# AutoTimer_List1.net
KiCad netlist of a schematic drawn in Altium Designer
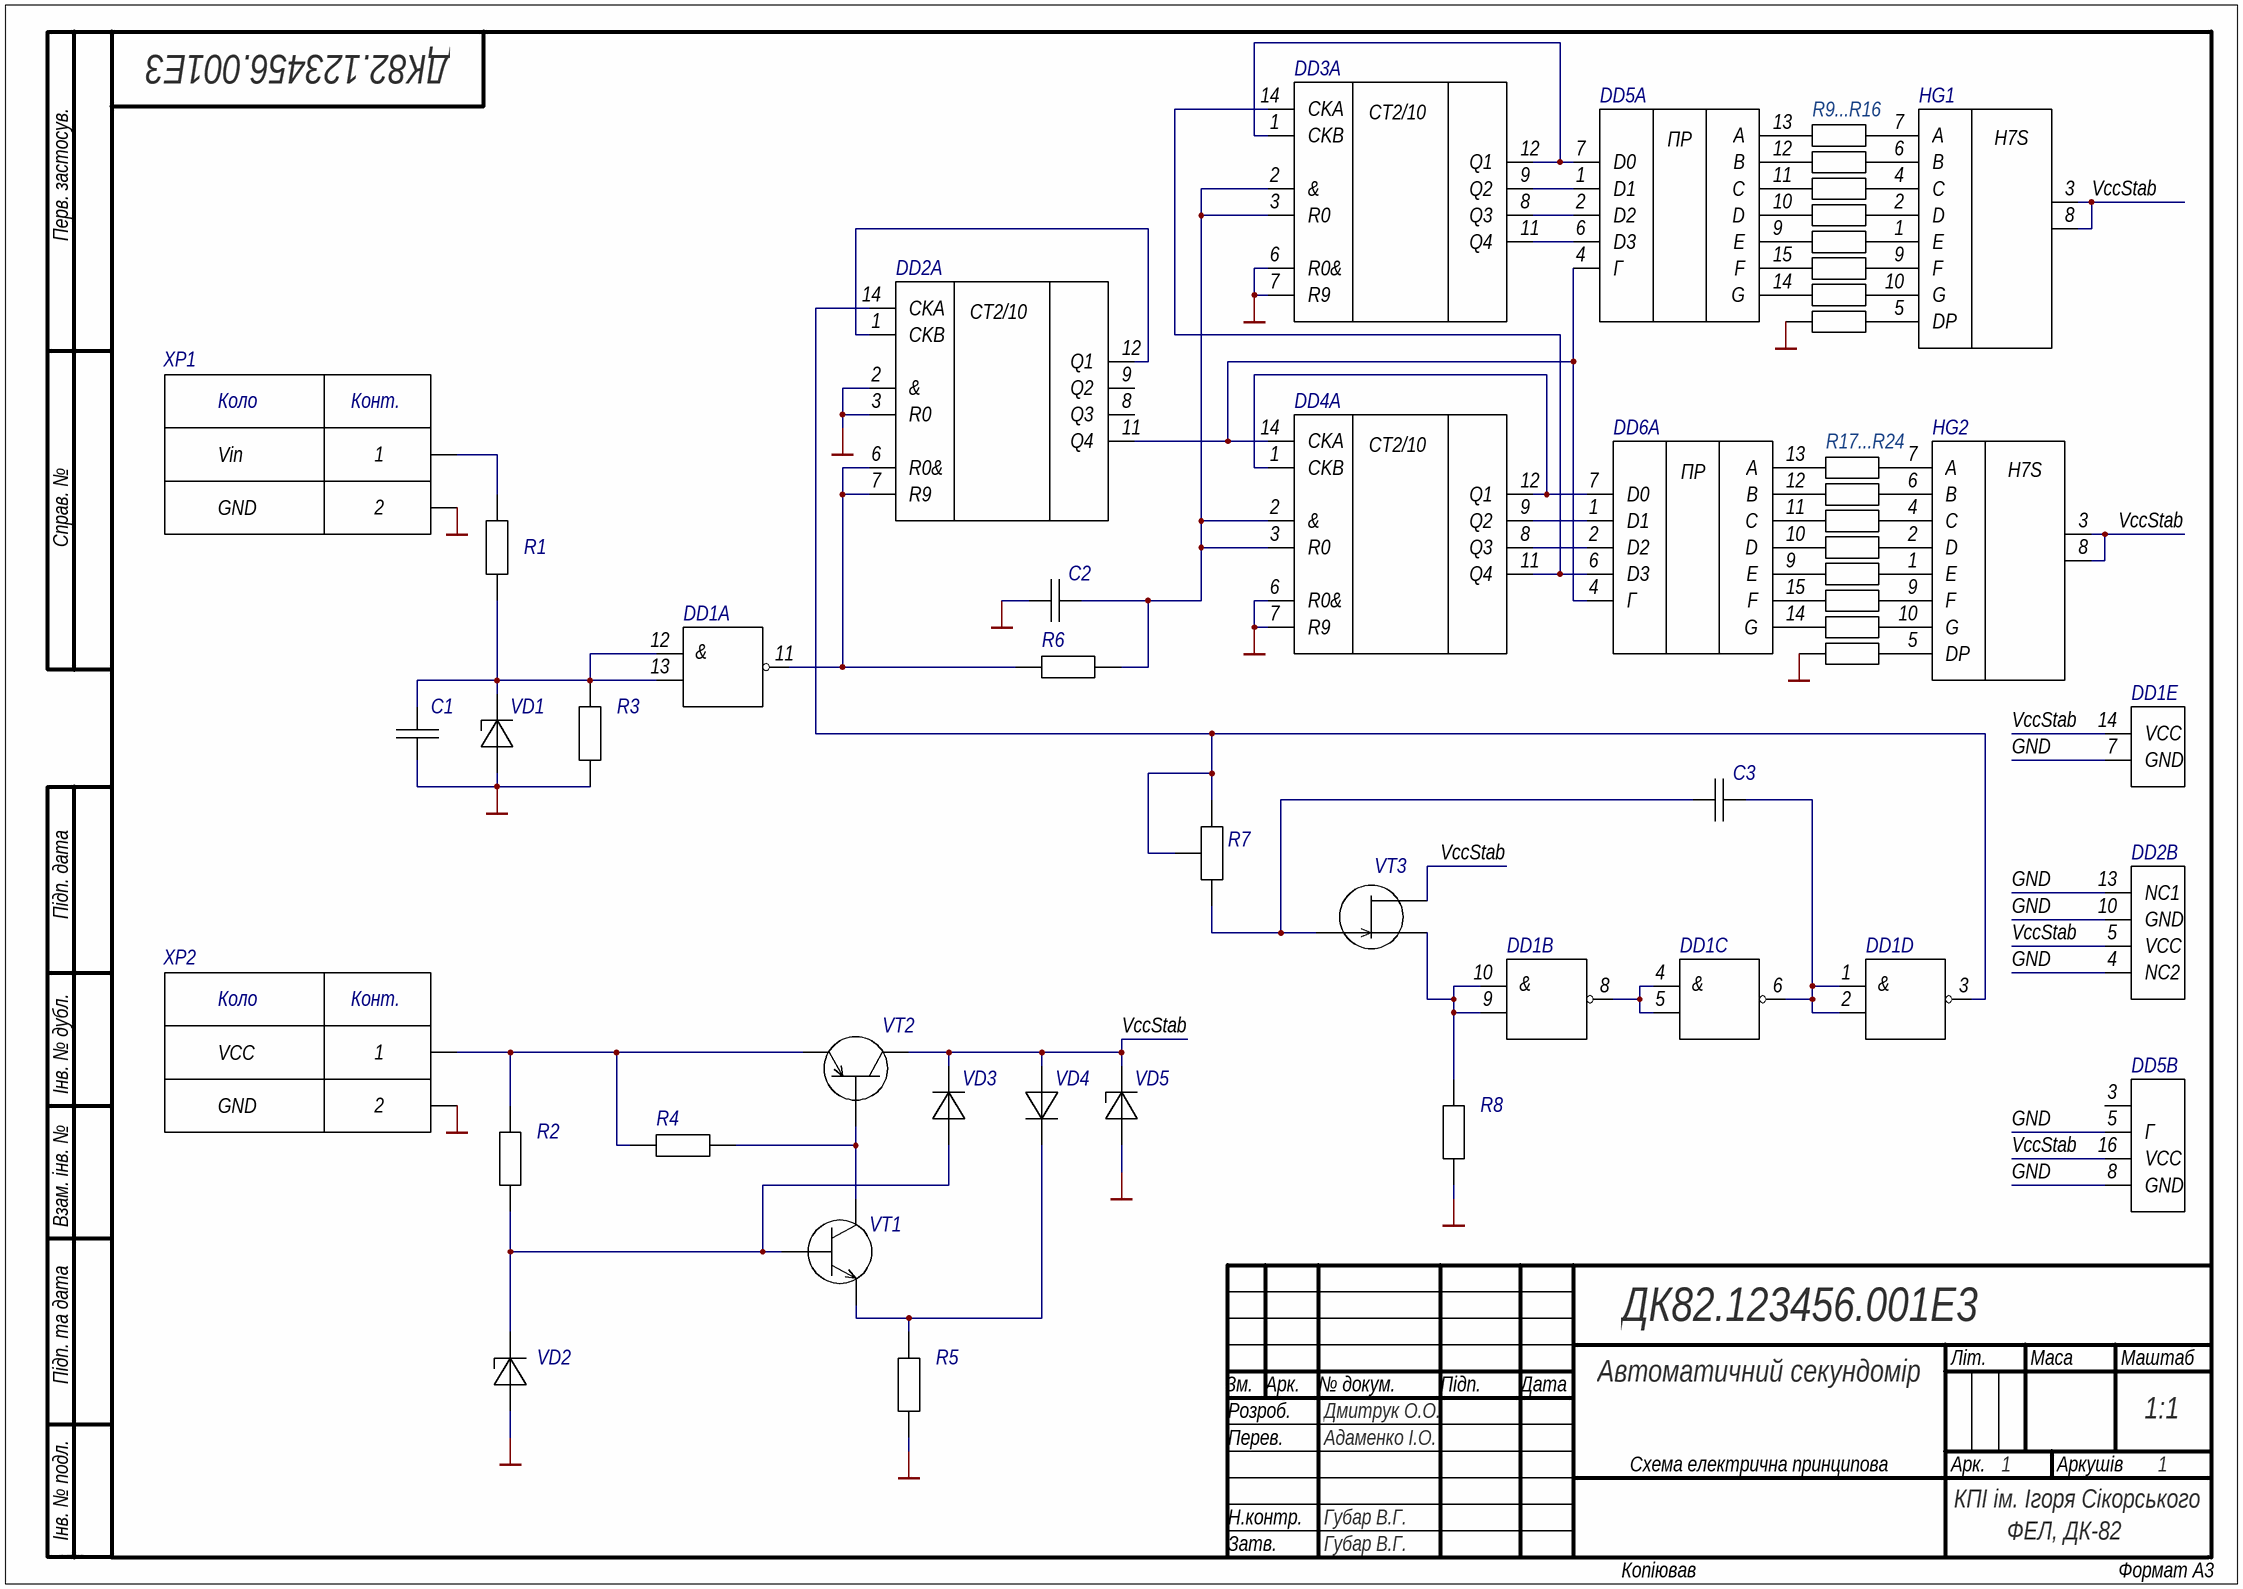
[diagram p0: AutoTimer_List1.SchDoc]

(export (version "E")
  (design (tool "Eeschema 10.0.6"))
  (components
    (comp (ref "C1")
      (value "С-0805 50 В 4,7 мкФ 10% X7R KEMET")
      (footprint "0805")
      (description "0805")
      (fields (field (name "VOLTAGE") "50 В") (field (name "TOLERANCE") "10%"))
      (libsource (lib "AutoTimer") (part "C-0805 4,7мкФ"))
    )
    (comp (ref "C2")
      (value "С-0805 50 В 1 мкФ 10% X7R KEMET")
      (footprint "0805")
      (description "0805")
      (fields (field (name "VOLTAGE") "50 В") (field (name "TOLERANCE") "10%"))
      (libsource (lib "AutoTimer") (part "C-0805 1мкФ"))
    )
    (comp (ref "C3")
      (value "С-0805 50 В 1 мкФ 10% X7R KEMET")
      (footprint "0805")
      (description "0805")
      (fields (field (name "VOLTAGE") "50 В") (field (name "TOLERANCE") "10%"))
      (libsource (lib "AutoTimer") (part "C-0805 1мкФ"))
    )
    (comp (ref "DD1")
      (value "SN74LS00 Texas Insturments")
      (footprint "SN74LS00 SN74LS90 FOOTPRINT")
      (fields
        (field (name "MANUFACTURER") "Texas Insturments")
        (field (name "COMPONENTLINK1URL") "file:///C:/Users/aleks/Downloads/Telegram%20Desktop/sn7400-sp.pdf")
      )
      (libsource (lib "AutoTimer") (part "SN74LS00"))
    )
    (comp (ref "DD2")
      (value "SN74LS90 Texas Insturments")
      (footprint "SN74LS00 SN74LS90 FOOTPRINT")
      (fields
        (field (name "MANUFACTURER") "Texas Insturments")
        (field (name "COMPONENTLINK1URL") "file:///C:/Users/aleks/Downloads/Telegram%20Desktop/SN7490AN.pdf")
      )
      (libsource (lib "AutoTimer") (part "SN74LS90"))
    )
    (comp (ref "DD3")
      (value "SN74LS90 Texas Insturments")
      (footprint "SN74LS00 SN74LS90 FOOTPRINT")
      (fields
        (field (name "MANUFACTURER") "Texas Insturments")
        (field (name "COMPONENTLINK1URL") "file:///C:/Users/aleks/Downloads/Telegram%20Desktop/SN7490AN.pdf")
      )
      (libsource (lib "AutoTimer") (part "SN74LS90"))
    )
    (comp (ref "DD4")
      (value "SN74LS90 Texas Insturments")
      (footprint "SN74LS00 SN74LS90 FOOTPRINT")
      (fields
        (field (name "MANUFACTURER") "Texas Insturments")
        (field (name "COMPONENTLINK1URL") "file:///C:/Users/aleks/Downloads/Telegram%20Desktop/SN7490AN.pdf")
      )
      (libsource (lib "AutoTimer") (part "SN74LS90"))
    )
    (comp (ref "DD5")
      (value "К514ПР1 *")
      (footprint "К514ПР1 FOOTPRINT")
      (libsource (lib "AutoTimer") (part "К514ПР1"))
    )
    (comp (ref "DD6")
      (value "К514ПР1 *")
      (footprint "К514ПР1 FOOTPRINT")
      (libsource (lib "AutoTimer") (part "К514ПР1"))
    )
    (comp (ref "HG1")
      (value "KCSA56-105 Kingbright")
      (footprint "KCSA56-105_FOOTPRINT")
      (fields (field (name "MANUFACTURER") "Kingbright"))
      (libsource (lib "AutoTimer") (part "KCSA56-105"))
    )
    (comp (ref "HG2")
      (value "KCSA56-105 Kingbright")
      (footprint "KCSA56-105_FOOTPRINT")
      (fields (field (name "MANUFACTURER") "Kingbright"))
      (libsource (lib "AutoTimer") (part "KCSA56-105"))
    )
    (comp (ref "R1")
      (value "R-0805 0,125 Вт 6,2 кОм 5% Yageo")
      (footprint "0805")
      (fields
        (field (name "POWER") "0,125 Вт")
        (field (name "TOLERANCE") "5%")
        (field (name "MANUFACTURER") "Yageo")
      )
      (libsource (lib "AutoTimer") (part "R-0805 6,2кОм"))
    )
    (comp (ref "R2")
      (value "R-0805 0,125 Вт 3 кОм 5% Yageo")
      (footprint "0805")
      (fields
        (field (name "POWER") "0,125 Вт")
        (field (name "TOLERANCE") "5%")
        (field (name "MANUFACTURER") "Yageo")
      )
      (libsource (lib "AutoTimer") (part "R-0805 3кОм"))
    )
    (comp (ref "R3")
      (value "R-0805 0,125 Вт 2 кОм 5% Yageo")
      (footprint "0805")
      (fields
        (field (name "POWER") "0,125 Вт")
        (field (name "TOLERANCE") "5%")
        (field (name "MANUFACTURER") "Yageo")
      )
      (libsource (lib "AutoTimer") (part "R-0805 2кОм"))
    )
    (comp (ref "R4")
      (value "R-0805 0,125 Вт 510 Ом 5% Yageo")
      (footprint "0805")
      (fields
        (field (name "POWER") "0,125 Вт")
        (field (name "TOLERANCE") "5%")
        (field (name "MANUFACTURER") "Yageo")
      )
      (libsource (lib "AutoTimer") (part "R-0805 510Ом"))
    )
    (comp (ref "R5")
      (value "R-0805 0,125 Вт 390 Ом 5% Yageo")
      (footprint "0805")
      (fields
        (field (name "POWER") "0,125 Вт")
        (field (name "TOLERANCE") "5%")
        (field (name "MANUFACTURER") "Yageo")
      )
      (libsource (lib "AutoTimer") (part "R-0805 390Ом"))
    )
    (comp (ref "R6")
      (value "R-0805 0,125 Вт 1,2 кОм 5% Yageo")
      (footprint "0805")
      (fields
        (field (name "POWER") "0,125 Вт")
        (field (name "TOLERANCE") "5%")
        (field (name "MANUFACTURER") "Yageo")
      )
      (libsource (lib "AutoTimer") (part "R-0805 1,2кОм"))
    )
    (comp (ref "R7")
      (value "3313J-1 0,125 Вт 10 кОм 20% Mouzer")
      (footprint "R-3313J-1 FOOTPRINT")
      (fields
        (field (name "POWER") "0,125 Вт")
        (field (name "TOLERANCE") "20%")
        (field (name "MANUFACTURER") "Mouzer")
      )
      (libsource (lib "AutoTimer") (part "R-3313J-1 10кОм"))
    )
    (comp (ref "R8")
      (value "R-0805 0,125 Вт 300 Ом 5% Yageo")
      (footprint "0805")
      (fields
        (field (name "POWER") "0,125 Вт")
        (field (name "TOLERANCE") "5%")
        (field (name "MANUFACTURER") "Yageo")
      )
      (libsource (lib "AutoTimer") (part "R-0805 300Ом"))
    )
    (comp (ref "R9")
      (value "R-0805 0,125 Вт 240 Ом 5% Yageo")
      (footprint "0805")
      (fields
        (field (name "POWER") "0,125 Вт")
        (field (name "TOLERANCE") "5%")
        (field (name "MANUFACTURER") "Yageo")
      )
      (libsource (lib "AutoTimer") (part "R-0805 240Ом"))
    )
    (comp (ref "R10")
      (value "R-0805 0,125 Вт 240 Ом 5% Yageo")
      (footprint "0805")
      (fields
        (field (name "POWER") "0,125 Вт")
        (field (name "TOLERANCE") "5%")
        (field (name "MANUFACTURER") "Yageo")
      )
      (libsource (lib "AutoTimer") (part "R-0805 240Ом"))
    )
    (comp (ref "R11")
      (value "R-0805 0,125 Вт 240 Ом 5% Yageo")
      (footprint "0805")
      (fields
        (field (name "POWER") "0,125 Вт")
        (field (name "TOLERANCE") "5%")
        (field (name "MANUFACTURER") "Yageo")
      )
      (libsource (lib "AutoTimer") (part "R-0805 240Ом"))
    )
    (comp (ref "R12")
      (value "R-0805 0,125 Вт 240 Ом 5% Yageo")
      (footprint "0805")
      (fields
        (field (name "POWER") "0,125 Вт")
        (field (name "TOLERANCE") "5%")
        (field (name "MANUFACTURER") "Yageo")
      )
      (libsource (lib "AutoTimer") (part "R-0805 240Ом"))
    )
    (comp (ref "R13")
      (value "R-0805 0,125 Вт 240 Ом 5% Yageo")
      (footprint "0805")
      (fields
        (field (name "POWER") "0,125 Вт")
        (field (name "TOLERANCE") "5%")
        (field (name "MANUFACTURER") "Yageo")
      )
      (libsource (lib "AutoTimer") (part "R-0805 240Ом"))
    )
    (comp (ref "R14")
      (value "R-0805 0,125 Вт 240 Ом 5% Yageo")
      (footprint "0805")
      (fields
        (field (name "POWER") "0,125 Вт")
        (field (name "TOLERANCE") "5%")
        (field (name "MANUFACTURER") "Yageo")
      )
      (libsource (lib "AutoTimer") (part "R-0805 240Ом"))
    )
    (comp (ref "R15")
      (value "R-0805 0,125 Вт 240 Ом 5% Yageo")
      (footprint "0805")
      (fields
        (field (name "POWER") "0,125 Вт")
        (field (name "TOLERANCE") "5%")
        (field (name "MANUFACTURER") "Yageo")
      )
      (libsource (lib "AutoTimer") (part "R-0805 240Ом"))
    )
    (comp (ref "R16")
      (value "R-0805 0,125 Вт 240 Ом 5% Yageo")
      (footprint "0805")
      (fields
        (field (name "POWER") "0,125 Вт")
        (field (name "TOLERANCE") "5%")
        (field (name "MANUFACTURER") "Yageo")
      )
      (libsource (lib "AutoTimer") (part "R-0805 240Ом"))
    )
    (comp (ref "R17")
      (value "R-0805 0,125 Вт 240 Ом 5% Yageo")
      (footprint "0805")
      (fields
        (field (name "POWER") "0,125 Вт")
        (field (name "TOLERANCE") "5%")
        (field (name "MANUFACTURER") "Yageo")
      )
      (libsource (lib "AutoTimer") (part "R-0805 240Ом"))
    )
    (comp (ref "R18")
      (value "R-0805 0,125 Вт 240 Ом 5% Yageo")
      (footprint "0805")
      (fields
        (field (name "POWER") "0,125 Вт")
        (field (name "TOLERANCE") "5%")
        (field (name "MANUFACTURER") "Yageo")
      )
      (libsource (lib "AutoTimer") (part "R-0805 240Ом"))
    )
    (comp (ref "R19")
      (value "R-0805 0,125 Вт 240 Ом 5% Yageo")
      (footprint "0805")
      (fields
        (field (name "POWER") "0,125 Вт")
        (field (name "TOLERANCE") "5%")
        (field (name "MANUFACTURER") "Yageo")
      )
      (libsource (lib "AutoTimer") (part "R-0805 240Ом"))
    )
    (comp (ref "R20")
      (value "R-0805 0,125 Вт 240 Ом 5% Yageo")
      (footprint "0805")
      (fields
        (field (name "POWER") "0,125 Вт")
        (field (name "TOLERANCE") "5%")
        (field (name "MANUFACTURER") "Yageo")
      )
      (libsource (lib "AutoTimer") (part "R-0805 240Ом"))
    )
    (comp (ref "R21")
      (value "R-0805 0,125 Вт 240 Ом 5% Yageo")
      (footprint "0805")
      (fields
        (field (name "POWER") "0,125 Вт")
        (field (name "TOLERANCE") "5%")
        (field (name "MANUFACTURER") "Yageo")
      )
      (libsource (lib "AutoTimer") (part "R-0805 240Ом"))
    )
    (comp (ref "R22")
      (value "R-0805 0,125 Вт 240 Ом 5% Yageo")
      (footprint "0805")
      (fields
        (field (name "POWER") "0,125 Вт")
        (field (name "TOLERANCE") "5%")
        (field (name "MANUFACTURER") "Yageo")
      )
      (libsource (lib "AutoTimer") (part "R-0805 240Ом"))
    )
    (comp (ref "R23")
      (value "R-0805 0,125 Вт 240 Ом 5% Yageo")
      (footprint "0805")
      (fields
        (field (name "POWER") "0,125 Вт")
        (field (name "TOLERANCE") "5%")
        (field (name "MANUFACTURER") "Yageo")
      )
      (libsource (lib "AutoTimer") (part "R-0805 240Ом"))
    )
    (comp (ref "R24")
      (value "R-0805 0,125 Вт 240 Ом 5% Yageo")
      (footprint "0805")
      (fields
        (field (name "POWER") "0,125 Вт")
        (field (name "TOLERANCE") "5%")
        (field (name "MANUFACTURER") "Yageo")
      )
      (libsource (lib "AutoTimer") (part "R-0805 240Ом"))
    )
    (comp (ref "VD1")
      (value "1N4624 BSC")
      (footprint "DO-213")
      (description "DO-213")
      (fields (field (name "MANUFACTURER") "BSC"))
      (libsource (lib "AutoTimer") (part "1N4624"))
    )
    (comp (ref "VD2")
      (value "1N4624 BSC")
      (footprint "DO-213")
      (description "DO-213")
      (fields (field (name "MANUFACTURER") "BSC"))
      (libsource (lib "AutoTimer") (part "1N4624"))
    )
    (comp (ref "VD3")
      (value "1N533B MICROSEMI")
      (footprint "T-18")
      (description "T-18")
      (fields (field (name "MANUFACTURER") "MICROSEMI"))
      (libsource (lib "AutoTimer") (part "1N533B"))
    )
    (comp (ref "VD4")
      (value "1N533B MICROSEMI")
      (footprint "T-18")
      (description "T-18")
      (fields (field (name "MANUFACTURER") "MICROSEMI"))
      (libsource (lib "AutoTimer") (part "1N533B"))
    )
    (comp (ref "VD5")
      (value "1N710A MICROCHIP")
      (footprint "DO-35")
      (description "DO-35")
      (fields (field (name "MANUFACTURER") "MICROCHIP"))
      (libsource (lib "AutoTimer") (part "1N710A"))
    )
    (comp (ref "VT1")
      (value "BD233 SavantIC")
      (footprint "ТО-126")
      (description "TO-126")
      (fields (field (name "MANUFACTURER") "SavantIC"))
      (libsource (lib "AutoTimer") (part "BD233"))
    )
    (comp (ref "VT2")
      (value "2N5887 ETC")
      (footprint "TO66")
      (description "TO66")
      (fields (field (name "MANUFACTURER") "ETC"))
      (libsource (lib "AutoTimer") (part "2N5887"))
    )
    (comp (ref "VT3")
      (value "2N3458 MOTOROLA")
      (footprint "SOT23")
      (description "SOT23")
      (fields (field (name "MANUFACTURER") "MOTOROLA"))
      (libsource (lib "AutoTimer") (part "2N3458"))
    )
    (comp (ref "XP1")
      (value "DS1021 Ningbo Zhenqin Electronic")
      (footprint "PLS-2")
      (description "PLS-2_1x2")
      (fields (field (name "MANUFACTURER") "Ningbo Zhenqin Electronic"))
      (libsource (lib "AutoTimer") (part "DS1021"))
    )
    (comp (ref "XP2")
      (value "DS1021 Ningbo Zhenqin Electronic")
      (footprint "PLS-2")
      (description "PLS-2_1x2")
      (fields (field (name "MANUFACTURER") "Ningbo Zhenqin Electronic"))
      (libsource (lib "AutoTimer") (part "DS1021"))
    )
  )
  (nets
    (net (code "1") (name "/VccStab") (class "Default")
      (node (ref "DD1") (pin "14") (pinfunction "VCC_14") (pintype "passive"))
      (node (ref "DD2") (pin "5") (pinfunction "VCC_5") (pintype "passive"))
      (node (ref "DD5") (pin "16") (pinfunction "VCC_16") (pintype "passive"))
      (node (ref "HG1") (pin "3") (pintype "passive"))
      (node (ref "HG1") (pin "8") (pintype "passive"))
      (node (ref "HG2") (pin "3") (pintype "passive"))
      (node (ref "HG2") (pin "8") (pintype "passive"))
      (node (ref "VD3") (pin "2") (pinfunction "2_2") (pintype "passive"))
      (node (ref "VD4") (pin "1") (pinfunction "1_1") (pintype "passive"))
      (node (ref "VD5") (pin "2") (pinfunction "2_2") (pintype "passive"))
      (node (ref "VT2") (pin "2") (pinfunction "2_2") (pintype "passive"))
      (node (ref "VT3") (pin "1") (pinfunction "Source_1") (pintype "passive"))
    )
    (net (code "2") (name "GND") (class "Default")
      (node (ref "C1") (pin "1") (pinfunction "1_1") (pintype "passive"))
      (node (ref "C2") (pin "2") (pinfunction "2_2") (pintype "passive"))
      (node (ref "DD1") (pin "7") (pinfunction "GND_7") (pintype "passive"))
      (node (ref "DD2") (pin "10") (pinfunction "GND_10") (pintype "passive"))
      (node (ref "DD2") (pin "13") (pinfunction "NC1_13") (pintype "passive"))
      (node (ref "DD2") (pin "2") (pinfunction "&_2") (pintype "passive"))
      (node (ref "DD2") (pin "3") (pinfunction "R0_3") (pintype "passive"))
      (node (ref "DD2") (pin "4") (pinfunction "NC2_4") (pintype "passive"))
      (node (ref "DD3") (pin "6") (pinfunction "R0&_6") (pintype "passive"))
      (node (ref "DD3") (pin "7") (pinfunction "R9_7") (pintype "passive"))
      (node (ref "DD4") (pin "6") (pinfunction "R0&_6") (pintype "passive"))
      (node (ref "DD4") (pin "7") (pinfunction "R9_7") (pintype "passive"))
      (node (ref "DD5") (pin "5") (pinfunction "Г_5") (pintype "passive"))
      (node (ref "DD5") (pin "8") (pinfunction "GND_8") (pintype "passive"))
      (node (ref "R16") (pin "1") (pinfunction "1_1") (pintype "passive"))
      (node (ref "R24") (pin "1") (pinfunction "1_1") (pintype "passive"))
      (node (ref "R3") (pin "1") (pinfunction "1_1") (pintype "passive"))
      (node (ref "R5") (pin "1") (pinfunction "1_1") (pintype "passive"))
      (node (ref "R8") (pin "1") (pinfunction "1_1") (pintype "passive"))
      (node (ref "VD1") (pin "1") (pinfunction "1_1") (pintype "passive"))
      (node (ref "VD2") (pin "1") (pinfunction "1_1") (pintype "passive"))
      (node (ref "VD5") (pin "1") (pinfunction "1_1") (pintype "passive"))
      (node (ref "XP1") (pin "2") (pinfunction "2_2") (pintype "passive"))
      (node (ref "XP2") (pin "2") (pinfunction "2_2") (pintype "passive"))
    )
    (net (code "3") (name "Net-(C1-Pad2)") (class "Default")
      (node (ref "C1") (pin "2") (pinfunction "2_2") (pintype "passive"))
      (node (ref "DD1") (pin "12") (pintype "passive"))
      (node (ref "DD1") (pin "13") (pintype "passive"))
      (node (ref "R1") (pin "1") (pinfunction "1_1") (pintype "passive"))
      (node (ref "R3") (pin "2") (pinfunction "2_2") (pintype "passive"))
      (node (ref "VD1") (pin "2") (pinfunction "2_2") (pintype "passive"))
    )
    (net (code "4") (name "Net-(C3-Pad2)") (class "Default")
      (node (ref "C3") (pin "2") (pinfunction "2_2") (pintype "passive"))
      (node (ref "DD1") (pin "1") (pintype "passive"))
      (node (ref "DD1") (pin "2") (pintype "passive"))
      (node (ref "DD1") (pin "6") (pintype "passive"))
    )
    (net (code "5") (name "Net-(DD1-Pad4)") (class "Default")
      (node (ref "DD1") (pin "4") (pintype "passive"))
      (node (ref "DD1") (pin "5") (pintype "passive"))
      (node (ref "DD1") (pin "8") (pintype "passive"))
    )
    (net (code "6") (name "Net-(DD2A-CKA)") (class "Default")
      (node (ref "DD1") (pin "3") (pintype "passive"))
      (node (ref "DD2") (pin "14") (pinfunction "CKA_14") (pintype "passive"))
      (node (ref "R7") (pin "2") (pinfunction "2_2") (pintype "passive"))
      (node (ref "R7") (pin "3") (pinfunction "3_3") (pintype "passive"))
    )
    (net (code "7") (name "Net-(DD2A-CKB)") (class "Default")
      (node (ref "DD2") (pin "1") (pinfunction "CKB_1") (pintype "passive"))
      (node (ref "DD2") (pin "12") (pinfunction "Q1_12") (pintype "passive"))
    )
    (net (code "8") (name "Net-(DD2A-Q4)") (class "Default")
      (node (ref "DD2") (pin "11") (pinfunction "Q4_11") (pintype "passive"))
      (node (ref "DD4") (pin "14") (pinfunction "CKA_14") (pintype "passive"))
      (node (ref "DD5") (pin "4") (pinfunction "Г_4") (pintype "passive"))
      (node (ref "DD6") (pin "4") (pinfunction "Г_4") (pintype "passive"))
    )
    (net (code "9") (name "Net-(DD2A-R0&)") (class "Default")
      (node (ref "DD1") (pin "11") (pintype "passive"))
      (node (ref "DD2") (pin "6") (pinfunction "R0&_6") (pintype "passive"))
      (node (ref "DD2") (pin "7") (pinfunction "R9_7") (pintype "passive"))
      (node (ref "R6") (pin "2") (pinfunction "2_2") (pintype "passive"))
    )
    (net (code "10") (name "Net-(DD3A-&)") (class "Default")
      (node (ref "C2") (pin "1") (pinfunction "1_1") (pintype "passive"))
      (node (ref "DD3") (pin "2") (pinfunction "&_2") (pintype "passive"))
      (node (ref "DD3") (pin "3") (pinfunction "R0_3") (pintype "passive"))
      (node (ref "DD4") (pin "2") (pinfunction "&_2") (pintype "passive"))
      (node (ref "DD4") (pin "3") (pinfunction "R0_3") (pintype "passive"))
      (node (ref "R6") (pin "1") (pinfunction "1_1") (pintype "passive"))
    )
    (net (code "11") (name "Net-(DD3A-CKA)") (class "Default")
      (node (ref "DD3") (pin "14") (pinfunction "CKA_14") (pintype "passive"))
      (node (ref "DD4") (pin "11") (pinfunction "Q4_11") (pintype "passive"))
      (node (ref "DD6") (pin "6") (pinfunction "D3_6") (pintype "passive"))
    )
    (net (code "12") (name "Net-(DD3A-CKB)") (class "Default")
      (node (ref "DD3") (pin "1") (pinfunction "CKB_1") (pintype "passive"))
      (node (ref "DD3") (pin "12") (pinfunction "Q1_12") (pintype "passive"))
      (node (ref "DD5") (pin "7") (pinfunction "D0_7") (pintype "passive"))
    )
    (net (code "13") (name "Net-(DD3A-Q2)") (class "Default")
      (node (ref "DD3") (pin "9") (pinfunction "Q2_9") (pintype "passive"))
      (node (ref "DD5") (pin "1") (pinfunction "D1_1") (pintype "passive"))
    )
    (net (code "14") (name "Net-(DD3A-Q3)") (class "Default")
      (node (ref "DD3") (pin "8") (pinfunction "Q3_8") (pintype "passive"))
      (node (ref "DD5") (pin "2") (pinfunction "D2_2") (pintype "passive"))
    )
    (net (code "15") (name "Net-(DD3A-Q4)") (class "Default")
      (node (ref "DD3") (pin "11") (pinfunction "Q4_11") (pintype "passive"))
      (node (ref "DD5") (pin "6") (pinfunction "D3_6") (pintype "passive"))
    )
    (net (code "16") (name "Net-(DD4A-CKB)") (class "Default")
      (node (ref "DD4") (pin "1") (pinfunction "CKB_1") (pintype "passive"))
      (node (ref "DD4") (pin "12") (pinfunction "Q1_12") (pintype "passive"))
      (node (ref "DD6") (pin "7") (pinfunction "D0_7") (pintype "passive"))
    )
    (net (code "17") (name "Net-(DD4A-Q2)") (class "Default")
      (node (ref "DD4") (pin "9") (pinfunction "Q2_9") (pintype "passive"))
      (node (ref "DD6") (pin "1") (pinfunction "D1_1") (pintype "passive"))
    )
    (net (code "18") (name "Net-(DD4A-Q3)") (class "Default")
      (node (ref "DD4") (pin "8") (pinfunction "Q3_8") (pintype "passive"))
      (node (ref "DD6") (pin "2") (pinfunction "D2_2") (pintype "passive"))
    )
    (net (code "19") (name "Net-(DD5A-B)") (class "Default")
      (node (ref "DD5") (pin "12") (pinfunction "B_12") (pintype "passive"))
      (node (ref "R10") (pin "1") (pinfunction "1_1") (pintype "passive"))
    )
    (net (code "20") (name "Net-(DD5A-D)") (class "Default")
      (node (ref "DD5") (pin "10") (pinfunction "D_10") (pintype "passive"))
      (node (ref "R12") (pin "1") (pinfunction "1_1") (pintype "passive"))
    )
    (net (code "21") (name "Net-(DD5A-E)") (class "Default")
      (node (ref "DD5") (pin "9") (pinfunction "E_9") (pintype "passive"))
      (node (ref "R13") (pin "1") (pinfunction "1_1") (pintype "passive"))
    )
    (net (code "22") (name "Net-(DD5A-F)") (class "Default")
      (node (ref "DD5") (pin "15") (pinfunction "F_15") (pintype "passive"))
      (node (ref "R14") (pin "1") (pinfunction "1_1") (pintype "passive"))
    )
    (net (code "23") (name "Net-(DD5A-G)") (class "Default")
      (node (ref "DD5") (pin "14") (pinfunction "G_14") (pintype "passive"))
      (node (ref "R15") (pin "1") (pinfunction "1_1") (pintype "passive"))
    )
    (net (code "24") (name "Net-(DD5A-А)") (class "Default")
      (node (ref "DD5") (pin "13") (pinfunction "А_13") (pintype "passive"))
      (node (ref "R9") (pin "1") (pinfunction "1_1") (pintype "passive"))
    )
    (net (code "25") (name "Net-(DD5A-С)") (class "Default")
      (node (ref "DD5") (pin "11") (pinfunction "С_11") (pintype "passive"))
      (node (ref "R11") (pin "1") (pinfunction "1_1") (pintype "passive"))
    )
    (net (code "26") (name "Net-(DD6A-B)") (class "Default")
      (node (ref "DD6") (pin "12") (pinfunction "B_12") (pintype "passive"))
      (node (ref "R18") (pin "1") (pinfunction "1_1") (pintype "passive"))
    )
    (net (code "27") (name "Net-(DD6A-D)") (class "Default")
      (node (ref "DD6") (pin "10") (pinfunction "D_10") (pintype "passive"))
      (node (ref "R20") (pin "1") (pinfunction "1_1") (pintype "passive"))
    )
    (net (code "28") (name "Net-(DD6A-E)") (class "Default")
      (node (ref "DD6") (pin "9") (pinfunction "E_9") (pintype "passive"))
      (node (ref "R21") (pin "1") (pinfunction "1_1") (pintype "passive"))
    )
    (net (code "29") (name "Net-(DD6A-F)") (class "Default")
      (node (ref "DD6") (pin "15") (pinfunction "F_15") (pintype "passive"))
      (node (ref "R22") (pin "1") (pinfunction "1_1") (pintype "passive"))
    )
    (net (code "30") (name "Net-(DD6A-G)") (class "Default")
      (node (ref "DD6") (pin "14") (pinfunction "G_14") (pintype "passive"))
      (node (ref "R23") (pin "1") (pinfunction "1_1") (pintype "passive"))
    )
    (net (code "31") (name "Net-(DD6A-А)") (class "Default")
      (node (ref "DD6") (pin "13") (pinfunction "А_13") (pintype "passive"))
      (node (ref "R17") (pin "1") (pinfunction "1_1") (pintype "passive"))
    )
    (net (code "32") (name "Net-(DD6A-С)") (class "Default")
      (node (ref "DD6") (pin "11") (pinfunction "С_11") (pintype "passive"))
      (node (ref "R19") (pin "1") (pinfunction "1_1") (pintype "passive"))
    )
    (net (code "33") (name "Net-(HG1-A)") (class "Default")
      (node (ref "HG1") (pin "7") (pinfunction "A_7") (pintype "passive"))
      (node (ref "R9") (pin "2") (pinfunction "2_2") (pintype "passive"))
    )
    (net (code "34") (name "Net-(HG1-B)") (class "Default")
      (node (ref "HG1") (pin "6") (pinfunction "B_6") (pintype "passive"))
      (node (ref "R10") (pin "2") (pinfunction "2_2") (pintype "passive"))
    )
    (net (code "35") (name "Net-(HG1-C)") (class "Default")
      (node (ref "HG1") (pin "4") (pinfunction "C_4") (pintype "passive"))
      (node (ref "R11") (pin "2") (pinfunction "2_2") (pintype "passive"))
    )
    (net (code "36") (name "Net-(HG1-D)") (class "Default")
      (node (ref "HG1") (pin "2") (pinfunction "D_2") (pintype "passive"))
      (node (ref "R12") (pin "2") (pinfunction "2_2") (pintype "passive"))
    )
    (net (code "37") (name "Net-(HG1-DP)") (class "Default")
      (node (ref "HG1") (pin "5") (pinfunction "DP_5") (pintype "passive"))
      (node (ref "R16") (pin "2") (pinfunction "2_2") (pintype "passive"))
    )
    (net (code "38") (name "Net-(HG1-E)") (class "Default")
      (node (ref "HG1") (pin "1") (pinfunction "E_1") (pintype "passive"))
      (node (ref "R13") (pin "2") (pinfunction "2_2") (pintype "passive"))
    )
    (net (code "39") (name "Net-(HG1-F)") (class "Default")
      (node (ref "HG1") (pin "9") (pinfunction "F_9") (pintype "passive"))
      (node (ref "R14") (pin "2") (pinfunction "2_2") (pintype "passive"))
    )
    (net (code "40") (name "Net-(HG1-G)") (class "Default")
      (node (ref "HG1") (pin "10") (pinfunction "G_10") (pintype "passive"))
      (node (ref "R15") (pin "2") (pinfunction "2_2") (pintype "passive"))
    )
    (net (code "41") (name "Net-(HG2-A)") (class "Default")
      (node (ref "HG2") (pin "7") (pinfunction "A_7") (pintype "passive"))
      (node (ref "R17") (pin "2") (pinfunction "2_2") (pintype "passive"))
    )
    (net (code "42") (name "Net-(HG2-B)") (class "Default")
      (node (ref "HG2") (pin "6") (pinfunction "B_6") (pintype "passive"))
      (node (ref "R18") (pin "2") (pinfunction "2_2") (pintype "passive"))
    )
    (net (code "43") (name "Net-(HG2-C)") (class "Default")
      (node (ref "HG2") (pin "4") (pinfunction "C_4") (pintype "passive"))
      (node (ref "R19") (pin "2") (pinfunction "2_2") (pintype "passive"))
    )
    (net (code "44") (name "Net-(HG2-D)") (class "Default")
      (node (ref "HG2") (pin "2") (pinfunction "D_2") (pintype "passive"))
      (node (ref "R20") (pin "2") (pinfunction "2_2") (pintype "passive"))
    )
    (net (code "45") (name "Net-(HG2-DP)") (class "Default")
      (node (ref "HG2") (pin "5") (pinfunction "DP_5") (pintype "passive"))
      (node (ref "R24") (pin "2") (pinfunction "2_2") (pintype "passive"))
    )
    (net (code "46") (name "Net-(HG2-E)") (class "Default")
      (node (ref "HG2") (pin "1") (pinfunction "E_1") (pintype "passive"))
      (node (ref "R21") (pin "2") (pinfunction "2_2") (pintype "passive"))
    )
    (net (code "47") (name "Net-(HG2-F)") (class "Default")
      (node (ref "HG2") (pin "9") (pinfunction "F_9") (pintype "passive"))
      (node (ref "R22") (pin "2") (pinfunction "2_2") (pintype "passive"))
    )
    (net (code "48") (name "Net-(HG2-G)") (class "Default")
      (node (ref "HG2") (pin "10") (pinfunction "G_10") (pintype "passive"))
      (node (ref "R23") (pin "2") (pinfunction "2_2") (pintype "passive"))
    )
    (net (code "49") (name "Net-(R1-Pad2)") (class "Default")
      (node (ref "R1") (pin "2") (pinfunction "2_2") (pintype "passive"))
      (node (ref "XP1") (pin "1") (pinfunction "1_1") (pintype "passive"))
    )
    (net (code "50") (name "Net-(R2-Pad1)") (class "Default")
      (node (ref "R2") (pin "1") (pinfunction "1_1") (pintype "passive"))
      (node (ref "VD2") (pin "2") (pinfunction "2_2") (pintype "passive"))
      (node (ref "VD3") (pin "1") (pinfunction "1_1") (pintype "passive"))
      (node (ref "VT1") (pin "3") (pinfunction "3_3") (pintype "passive"))
    )
    (net (code "51") (name "Net-(R2-Pad2)") (class "Default")
      (node (ref "R2") (pin "2") (pinfunction "2_2") (pintype "passive"))
      (node (ref "R4") (pin "1") (pinfunction "1_1") (pintype "passive"))
      (node (ref "VT2") (pin "1") (pinfunction "1_1") (pintype "passive"))
      (node (ref "XP2") (pin "1") (pinfunction "1_1") (pintype "passive"))
    )
    (net (code "52") (name "Net-(R4-Pad2)") (class "Default")
      (node (ref "R4") (pin "2") (pinfunction "2_2") (pintype "passive"))
      (node (ref "VT1") (pin "2") (pinfunction "2_2") (pintype "passive"))
      (node (ref "VT2") (pin "3") (pinfunction "3_3") (pintype "passive"))
    )
    (net (code "53") (name "Net-(R5-Pad2)") (class "Default")
      (node (ref "R5") (pin "2") (pinfunction "2_2") (pintype "passive"))
      (node (ref "VD4") (pin "2") (pinfunction "2_2") (pintype "passive"))
      (node (ref "VT1") (pin "1") (pinfunction "1_1") (pintype "passive"))
    )
    (net (code "54") (name "Net-(VT3-Drain)") (class "Default")
      (node (ref "DD1") (pin "10") (pintype "passive"))
      (node (ref "DD1") (pin "9") (pintype "passive"))
      (node (ref "R8") (pin "2") (pinfunction "2_2") (pintype "passive"))
      (node (ref "VT3") (pin "2") (pinfunction "Drain_2") (pintype "passive"))
    )
    (net (code "55") (name "Net-(VT3-Gate)") (class "Default")
      (node (ref "C3") (pin "1") (pinfunction "1_1") (pintype "passive"))
      (node (ref "R7") (pin "1") (pinfunction "1_1") (pintype "passive"))
      (node (ref "VT3") (pin "3") (pinfunction "Gate_3") (pintype "passive"))
    )
    (net (code "56") (name "unconnected-(DD2A-Q2-Pad9)") (class "Default")
      (node (ref "DD2") (pin "9") (pinfunction "Q2_9") (pintype "passive"))
    )
    (net (code "57") (name "unconnected-(DD2A-Q3-Pad8)") (class "Default")
      (node (ref "DD2") (pin "8") (pinfunction "Q3_8") (pintype "passive"))
    )
    (net (code "58") (name "unconnected-(DD5-Pad3)") (class "Default")
      (node (ref "DD5") (pin "3") (pintype "passive"))
    )
  )
)
